# TamperEvidentAmplifier.net
KiCad netlist of a schematic drawn in EAGLE
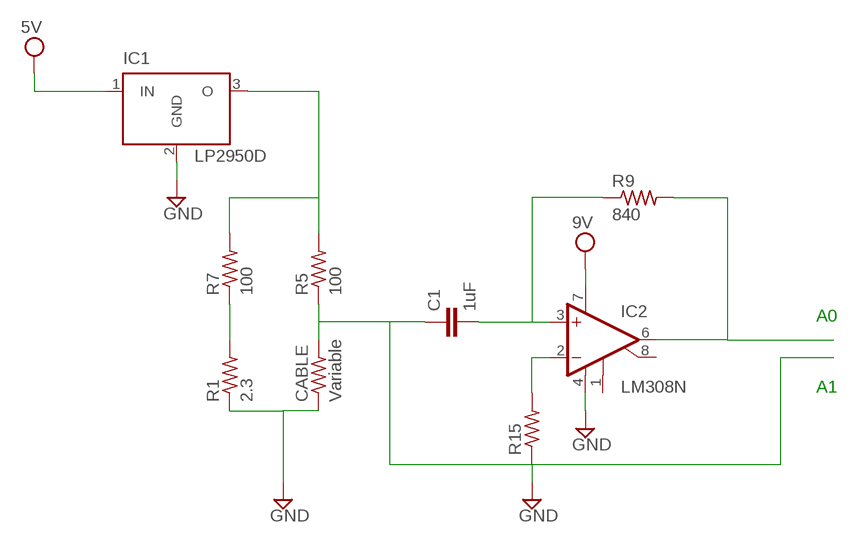
[diagram p0: schematic, sheet 1]

(export (version "E")
  (design (tool "Eeschema 10.0.6"))
  (components
    (comp (ref "C1")
      (value "1uF")
      (footprint "eagle-import:C7.5B6")
      (libsource (lib "eagle-import") (part "C7.5/6"))
    )
    (comp (ref "CABLE")
      (value "Variable")
      (footprint "eagle-import:0207_10")
      (libsource (lib "eagle-import") (part "R-US_0207/10"))
    )
    (comp (ref "IC1")
      (value "LP2950D")
      (footprint "eagle-import:TO252")
      (fields (field (name "MF") "NATIONAL SEMICONDUCTOR") (field (name "MPN") "LP2950CDT-5.0/NOPB"))
      (libsource (lib "eagle-import") (part "LP2950D"))
    )
    (comp (ref "IC2")
      (value "LM308N")
      (footprint "eagle-import:DIL08")
      (libsource (lib "eagle-import") (part "LM308N"))
    )
    (comp (ref "R1")
      (value "2.3")
      (footprint "eagle-import:0207_10")
      (libsource (lib "eagle-import") (part "R-US_0207/10"))
    )
    (comp (ref "R5")
      (value "100")
      (footprint "eagle-import:0207_10")
      (libsource (lib "eagle-import") (part "R-US_0207/10"))
    )
    (comp (ref "R7")
      (value "100")
      (footprint "eagle-import:0207_10")
      (libsource (lib "eagle-import") (part "R-US_0207/10"))
    )
    (comp (ref "R9")
      (value "840")
      (footprint "eagle-import:0207_10")
      (libsource (lib "eagle-import") (part "R-US_0207/10"))
    )
    (comp (ref "R15")
      (value "R-US_0207/10")
      (footprint "eagle-import:0207_10")
      (libsource (lib "eagle-import") (part "R-US_0207/10"))
    )
  )
  (nets
    (net (code "1") (name "5V") (class "Default")
      (node (ref "IC1") (pin "1") (pinfunction "IN_1") (pintype "input"))
      (node (ref "IC2") (pin "7") (pinfunction "V+_7") (pintype "power_in"))
    )
    (net (code "2") (name "GND") (class "Default")
      (node (ref "CABLE") (pin "1") (pinfunction "1_1") (pintype "passive"))
      (node (ref "IC1") (pin "2") (pinfunction "GND_2") (pintype "power_in"))
      (node (ref "IC2") (pin "4") (pinfunction "V-_4") (pintype "power_in"))
      (node (ref "R1") (pin "1") (pinfunction "1_1") (pintype "passive"))
      (node (ref "R15") (pin "1") (pinfunction "1_1") (pintype "passive"))
    )
    (net (code "3") (name "Net-(C1-Pad1)") (class "Default")
      (node (ref "C1") (pin "1") (pinfunction "1_1") (pintype "passive"))
      (node (ref "CABLE") (pin "2") (pinfunction "2_2") (pintype "passive"))
      (node (ref "R5") (pin "1") (pinfunction "1_1") (pintype "passive"))
    )
    (net (code "4") (name "Net-(IC1-O)") (class "Default")
      (node (ref "IC1") (pin "3") (pinfunction "O_3") (pintype "output"))
      (node (ref "R5") (pin "2") (pinfunction "2_2") (pintype "passive"))
      (node (ref "R7") (pin "2") (pinfunction "2_2") (pintype "passive"))
    )
    (net (code "5") (name "Net-(IC2-+IN)") (class "Default")
      (node (ref "C1") (pin "2") (pinfunction "2_2") (pintype "passive"))
      (node (ref "IC2") (pin "3") (pinfunction "+IN_3") (pintype "input"))
      (node (ref "R9") (pin "1") (pinfunction "1_1") (pintype "passive"))
    )
    (net (code "6") (name "Net-(IC2--IN)") (class "Default")
      (node (ref "IC2") (pin "2") (pinfunction "-IN_2") (pintype "input"))
      (node (ref "R15") (pin "2") (pinfunction "2_2") (pintype "passive"))
    )
    (net (code "7") (name "Net-(IC2-OUT)") (class "Default")
      (node (ref "IC2") (pin "6") (pinfunction "OUT_6") (pintype "output"))
      (node (ref "R9") (pin "2") (pinfunction "2_2") (pintype "passive"))
    )
    (net (code "8") (name "Net-(R1-Pad2)") (class "Default")
      (node (ref "R1") (pin "2") (pinfunction "2_2") (pintype "passive"))
      (node (ref "R7") (pin "1") (pinfunction "1_1") (pintype "passive"))
    )
    (net (code "9") (name "unconnected-(IC2-CMP1-Pad1)") (class "Default")
      (node (ref "IC2") (pin "1") (pinfunction "CMP1_1") (pintype "passive"))
    )
    (net (code "10") (name "unconnected-(IC2-CMP2-Pad8)") (class "Default")
      (node (ref "IC2") (pin "8") (pinfunction "CMP2_8") (pintype "passive"))
    )
  )
)
